# 05_-_FLASH.net
KiCad netlist of a schematic drawn in Altium Designer
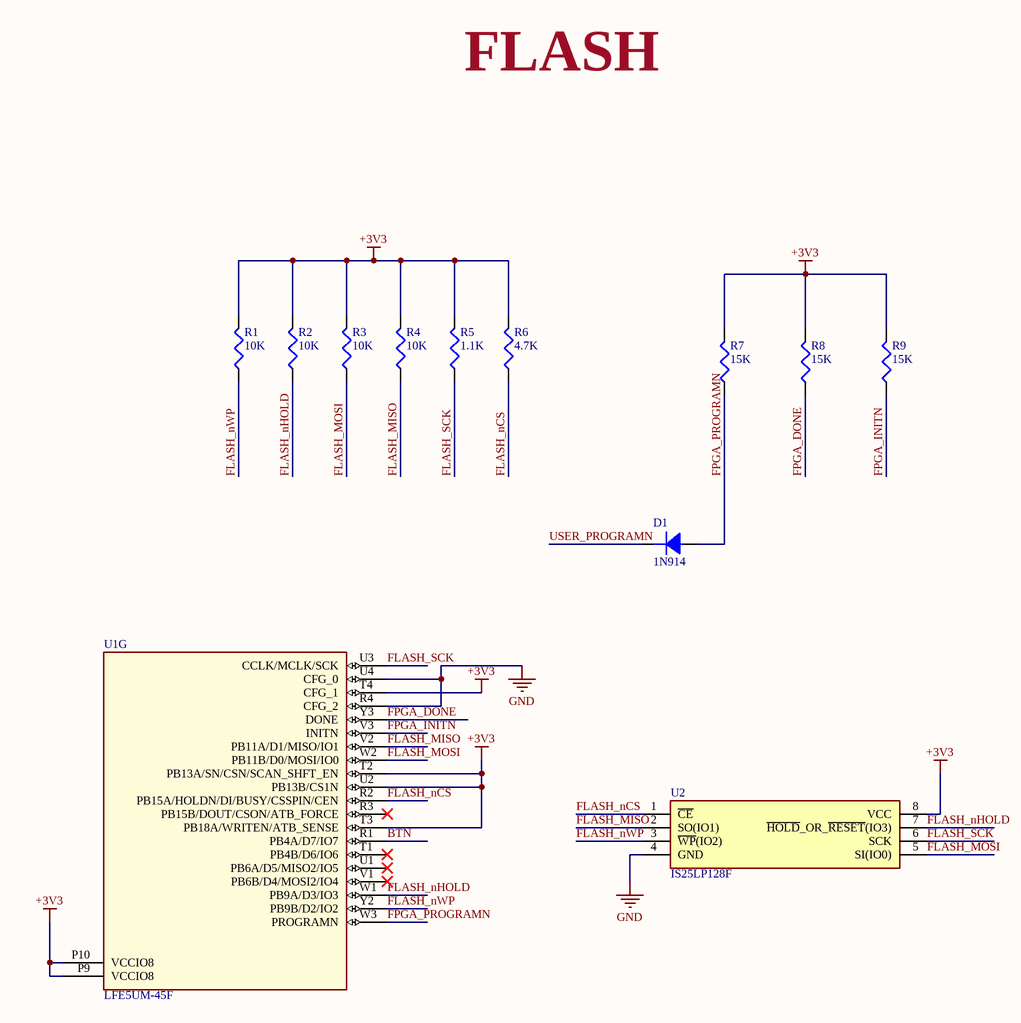
[diagram p0: [05] - FLASH.SchDoc]

(export (version "E")
  (design (tool "Eeschema 10.0.6"))
  (components
    (comp (ref "D1")
      (value "1N914")
      (footprint "SOD323")
      (description "ON SEMICONDUCTOR/FAIRCHILD - 1N914BWS. - SMALL SIGNAL DIODE")
      (fields
        (field (name "MANUFACTURER") "ON Semiconductor / Fairchild")
        (field (name "MANUFACTURER PART NUMBER") "1N914BWS")
      )
      (libsource (lib "ECP5_V2") (part "1N914BWS"))
    )
    (comp (ref "R1")
      (value "10K")
      (footprint "R0603")
      (description "Res General Purpose Thick Film 0603 10K Ohm 1% 1/10W ±100ppm/°C Molded SMD Paper T/R")
      (fields
        (field (name "MANUFACTURER") "Yageo")
        (field (name "MANUFACTURER PART NUMBER") "RC0603FR-0710KL")
      )
      (libsource (lib "ECP5_V2") (part "RC0603FR-0710KL"))
    )
    (comp (ref "R2")
      (value "10K")
      (footprint "R0603")
      (description "Res General Purpose Thick Film 0603 10K Ohm 1% 1/10W ±100ppm/°C Molded SMD Paper T/R")
      (fields
        (field (name "MANUFACTURER") "Yageo")
        (field (name "MANUFACTURER PART NUMBER") "RC0603FR-0710KL")
      )
      (libsource (lib "ECP5_V2") (part "RC0603FR-0710KL"))
    )
    (comp (ref "R3")
      (value "10K")
      (footprint "R0603")
      (description "Res General Purpose Thick Film 0603 10K Ohm 1% 1/10W ±100ppm/°C Molded SMD Paper T/R")
      (fields
        (field (name "MANUFACTURER") "Yageo")
        (field (name "MANUFACTURER PART NUMBER") "RC0603FR-0710KL")
      )
      (libsource (lib "ECP5_V2") (part "RC0603FR-0710KL"))
    )
    (comp (ref "R4")
      (value "10K")
      (footprint "R0603")
      (description "Res General Purpose Thick Film 0603 10K Ohm 1% 1/10W ±100ppm/°C Molded SMD Paper T/R")
      (fields
        (field (name "MANUFACTURER") "Yageo")
        (field (name "MANUFACTURER PART NUMBER") "RC0603FR-0710KL")
      )
      (libsource (lib "ECP5_V2") (part "RC0603FR-0710KL"))
    )
    (comp (ref "R5")
      (value "1.1K")
      (footprint "R0603")
      (description "RES SMD 1.1K OHM 1% 1/10W 0603")
      (fields
        (field (name "MANUFACTURER") "Yageo")
        (field (name "MANUFACTURER PART NUMBER") "RC0603FR-071K1L")
      )
      (libsource (lib "ECP5_V2") (part "RC0603FR-071K1L"))
    )
    (comp (ref "R6")
      (value "4.7K")
      (footprint "R0603")
      (description "RES SMD 4.7K OHM 1% 1/10W 0603")
      (fields
        (field (name "MANUFACTURER") "Yageo")
        (field (name "MANUFACTURER PART NUMBER") "RC0603FR-074K7L")
      )
      (libsource (lib "ECP5_V2") (part "RC0603FR-074K7L"))
    )
    (comp (ref "R7")
      (value "15K")
      (footprint "R0603")
      (description "Res Thick Film 0603 15K Ohm 1% 1/10W ?100ppm/?C Molded SMD Paper T/R")
      (fields
        (field (name "MANUFACTURER") "Yageo")
        (field (name "MANUFACTURER PART NUMBER") "RC0603FR-0715KL")
      )
      (libsource (lib "ECP5_V2") (part "RC0603FR-0715KL"))
    )
    (comp (ref "R8")
      (value "15K")
      (footprint "R0603")
      (description "Res Thick Film 0603 15K Ohm 1% 1/10W ?100ppm/?C Molded SMD Paper T/R")
      (fields
        (field (name "MANUFACTURER") "Yageo")
        (field (name "MANUFACTURER PART NUMBER") "RC0603FR-0715KL")
      )
      (libsource (lib "ECP5_V2") (part "RC0603FR-0715KL"))
    )
    (comp (ref "R9")
      (value "15K")
      (footprint "R0603")
      (description "Res Thick Film 0603 15K Ohm 1% 1/10W ?100ppm/?C Molded SMD Paper T/R")
      (fields
        (field (name "MANUFACTURER") "Yageo")
        (field (name "MANUFACTURER PART NUMBER") "RC0603FR-0715KL")
      )
      (libsource (lib "ECP5_V2") (part "RC0603FR-0715KL"))
    )
    (comp (ref "U1")
      (value "LFE5UM-45F")
      (footprint "LFE5BG381")
      (description "ECP5 Series 44 K LUTs 203 I/O 1.1 V Slow Surface Mount FPGA - CABGA-381")
      (fields
        (field (name "MANUFACTURER") "Lattice Semiconductor")
        (field (name "MANUFACTURER PART NUMBER") "LFE5UM-45F-6BG381C")
      )
      (libsource (lib "ECP5_V2") (part "LFE5UM-45F-6BG381C"))
    )
    (comp (ref "U2")
      (value "IS25LP128F")
      (footprint "SOIC127P790X216-8N")
      (description "IC FLASH 128M SPI 133MHZ 8SOIC")
      (fields
        (field (name "MANUFACTURER") "ISSI")
        (field (name "MANUFACTURER PART NUMBER") "IS25LP128F-JBLE")
      )
      (libsource (lib "ECP5_V2") (part "IS25LP128F-JBLE"))
    )
  )
  (nets
    (net (code "1") (name "+3V3") (class "Default")
      (node (ref "R1") (pin "2") (pinfunction "2_2") (pintype "passive"))
      (node (ref "R2") (pin "2") (pinfunction "2_2") (pintype "passive"))
      (node (ref "R3") (pin "2") (pinfunction "2_2") (pintype "passive"))
      (node (ref "R4") (pin "2") (pinfunction "2_2") (pintype "passive"))
      (node (ref "R5") (pin "2") (pinfunction "2_2") (pintype "passive"))
      (node (ref "R6") (pin "2") (pinfunction "2_2") (pintype "passive"))
      (node (ref "R7") (pin "2") (pinfunction "2_2") (pintype "passive"))
      (node (ref "R8") (pin "2") (pinfunction "2_2") (pintype "passive"))
      (node (ref "R9") (pin "2") (pinfunction "2_2") (pintype "passive"))
      (node (ref "U1") (pin "P10") (pinfunction "VCCIO8_P10") (pintype "power_in"))
      (node (ref "U1") (pin "P9") (pinfunction "VCCIO8_P9") (pintype "power_in"))
      (node (ref "U1") (pin "T2") (pinfunction "PB13A/SN/CSN/SCAN_SHFT_EN_T2") (pintype "bidirectional"))
      (node (ref "U1") (pin "T3") (pinfunction "PB18A/WRITEN/ATB_SENSE_T3") (pintype "bidirectional"))
      (node (ref "U1") (pin "T4") (pinfunction "CFG_1_T4") (pintype "bidirectional"))
      (node (ref "U1") (pin "U2") (pinfunction "PB13B/CS1N_U2") (pintype "bidirectional"))
      (node (ref "U2") (pin "8") (pinfunction "VCC_8") (pintype "passive"))
    )
    (net (code "2") (name "/BTN") (class "Default")
      (node (ref "U1") (pin "R1") (pinfunction "PB4A/D7/IO7_R1") (pintype "bidirectional"))
    )
    (net (code "3") (name "/FLASH_MISO") (class "Default")
      (node (ref "R4") (pin "1") (pinfunction "1_1") (pintype "passive"))
      (node (ref "U1") (pin "V2") (pinfunction "PB11A/D1/MISO/IO1_V2") (pintype "bidirectional"))
      (node (ref "U2") (pin "2") (pinfunction "SO(IO1)_2") (pintype "passive"))
    )
    (net (code "4") (name "/FLASH_MOSI") (class "Default")
      (node (ref "R3") (pin "1") (pinfunction "1_1") (pintype "passive"))
      (node (ref "U1") (pin "W2") (pinfunction "PB11B/D0/MOSI/IO0_W2") (pintype "bidirectional"))
      (node (ref "U2") (pin "5") (pinfunction "SI(IO0)_5") (pintype "passive"))
    )
    (net (code "5") (name "/FLASH_SCK") (class "Default")
      (node (ref "R5") (pin "1") (pinfunction "1_1") (pintype "passive"))
      (node (ref "U1") (pin "U3") (pinfunction "CCLK/MCLK/SCK_U3") (pintype "bidirectional"))
      (node (ref "U2") (pin "6") (pinfunction "SCK_6") (pintype "passive"))
    )
    (net (code "6") (name "/FLASH_nCS") (class "Default")
      (node (ref "R6") (pin "1") (pinfunction "1_1") (pintype "passive"))
      (node (ref "U1") (pin "R2") (pinfunction "PB15A/HOLDN/DI/BUSY/CSSPIN/CEN_R2") (pintype "bidirectional"))
      (node (ref "U2") (pin "1") (pinfunction "~{CE}_1") (pintype "passive"))
    )
    (net (code "7") (name "/FLASH_nHOLD") (class "Default")
      (node (ref "R2") (pin "1") (pinfunction "1_1") (pintype "passive"))
      (node (ref "U1") (pin "W1") (pinfunction "PB9A/D3/IO3_W1") (pintype "bidirectional"))
      (node (ref "U2") (pin "7") (pinfunction "~{HOLD}_OR_~{RESET}(IO3)_7") (pintype "passive"))
    )
    (net (code "8") (name "/FLASH_nWP") (class "Default")
      (node (ref "R1") (pin "1") (pinfunction "1_1") (pintype "passive"))
      (node (ref "U1") (pin "Y2") (pinfunction "PB9B/D2/IO2_Y2") (pintype "bidirectional"))
      (node (ref "U2") (pin "3") (pinfunction "~{WP}(IO2)_3") (pintype "passive"))
    )
    (net (code "9") (name "/FPGA_DONE") (class "Default")
      (node (ref "R8") (pin "1") (pinfunction "1_1") (pintype "passive"))
      (node (ref "U1") (pin "Y3") (pinfunction "DONE_Y3") (pintype "bidirectional"))
    )
    (net (code "10") (name "/FPGA_INITN") (class "Default")
      (node (ref "R9") (pin "1") (pinfunction "1_1") (pintype "passive"))
      (node (ref "U1") (pin "V3") (pinfunction "INITN_V3") (pintype "bidirectional"))
    )
    (net (code "11") (name "/FPGA_PROGRAMN") (class "Default")
      (node (ref "D1") (pin "2") (pinfunction "Anode_2") (pintype "passive"))
      (node (ref "R7") (pin "1") (pinfunction "1_1") (pintype "passive"))
      (node (ref "U1") (pin "W3") (pinfunction "PROGRAMN_W3") (pintype "bidirectional"))
    )
    (net (code "12") (name "/USER_PROGRAMN") (class "Default")
      (node (ref "D1") (pin "1") (pinfunction "Cathode_1") (pintype "passive"))
    )
    (net (code "13") (name "GND") (class "Default")
      (node (ref "U1") (pin "R4") (pinfunction "CFG_2_R4") (pintype "bidirectional"))
      (node (ref "U1") (pin "U4") (pinfunction "CFG_0_U4") (pintype "bidirectional"))
      (node (ref "U2") (pin "4") (pinfunction "GND_4") (pintype "passive"))
    )
    (net (code "14") (name "unconnected-(U1G-PB4B{slash}D6{slash}IO6-PadT1)") (class "Default")
      (node (ref "U1") (pin "T1") (pinfunction "PB4B/D6/IO6_T1") (pintype "bidirectional+no_connect"))
    )
    (net (code "15") (name "unconnected-(U1G-PB6A{slash}D5{slash}MISO2{slash}IO5-PadU1)") (class "Default")
      (node (ref "U1") (pin "U1") (pinfunction "PB6A/D5/MISO2/IO5_U1") (pintype "bidirectional+no_connect"))
    )
    (net (code "16") (name "unconnected-(U1G-PB6B{slash}D4{slash}MOSI2{slash}IO4-PadV1)") (class "Default")
      (node (ref "U1") (pin "V1") (pinfunction "PB6B/D4/MOSI2/IO4_V1") (pintype "bidirectional+no_connect"))
    )
    (net (code "17") (name "unconnected-(U1G-PB15B{slash}DOUT{slash}CSON{slash}ATB_FORCE-PadR3)") (class "Default")
      (node (ref "U1") (pin "R3") (pinfunction "PB15B/DOUT/CSON/ATB_FORCE_R3") (pintype "bidirectional+no_connect"))
    )
  )
)
